# sw_xz.net
KiCad netlist of a schematic drawn in EAGLE
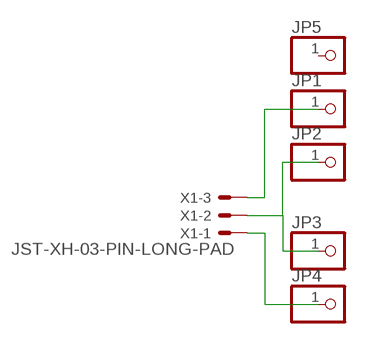
[diagram p0: schematic, sheet 1]

(export (version "E")
  (design (tool "Eeschema 10.0.6"))
  (components
    (comp (ref "JP1")
      (value "PINHD-1X1")
      (footprint "eagle-import:1X01")
      (libsource (lib "eagle-import") (part "PINHD-1X1"))
    )
    (comp (ref "JP2")
      (value "PINHD-1X1")
      (footprint "eagle-import:1X01")
      (libsource (lib "eagle-import") (part "PINHD-1X1"))
    )
    (comp (ref "JP3")
      (value "PINHD-1X1")
      (footprint "eagle-import:1X01")
      (libsource (lib "eagle-import") (part "PINHD-1X1"))
    )
    (comp (ref "JP4")
      (value "PINHD-1X1")
      (footprint "eagle-import:1X01")
      (libsource (lib "eagle-import") (part "PINHD-1X1"))
    )
    (comp (ref "JP5")
      (value "PINHD-1X1")
      (footprint "eagle-import:1X01")
      (libsource (lib "eagle-import") (part "PINHD-1X1"))
    )
    (comp (ref "X1")
      (value "JST-XH-03-PIN-LONG-PAD")
      (footprint "eagle-import:JST-XH-03-PACKAGE-LONG-PAD")
      (libsource (lib "eagle-import") (part "JST-XH-03-PIN-LONG-PAD"))
    )
  )
  (nets
    (net (code "1") (name "Net-(X1A-S)") (class "Default")
      (node (ref "JP4") (pin "1") (pinfunction "1_1") (pintype "passive"))
      (node (ref "X1") (pin "1") (pinfunction "S_1") (pintype "passive"))
    )
    (net (code "2") (name "Net-(X1B-S)") (class "Default")
      (node (ref "JP2") (pin "1") (pinfunction "1_1") (pintype "passive"))
      (node (ref "JP3") (pin "1") (pinfunction "1_1") (pintype "passive"))
      (node (ref "X1") (pin "2") (pinfunction "S_2") (pintype "passive"))
    )
    (net (code "3") (name "Net-(X1C-S)") (class "Default")
      (node (ref "JP1") (pin "1") (pinfunction "1_1") (pintype "passive"))
      (node (ref "X1") (pin "3") (pinfunction "S_3") (pintype "passive"))
    )
    (net (code "4") (name "unconnected-(JP5-Pad1)") (class "Default")
      (node (ref "JP5") (pin "1") (pinfunction "1_1") (pintype "passive"))
    )
  )
)
